# WireHub_2.net
KiCad netlist of a schematic drawn in EAGLE
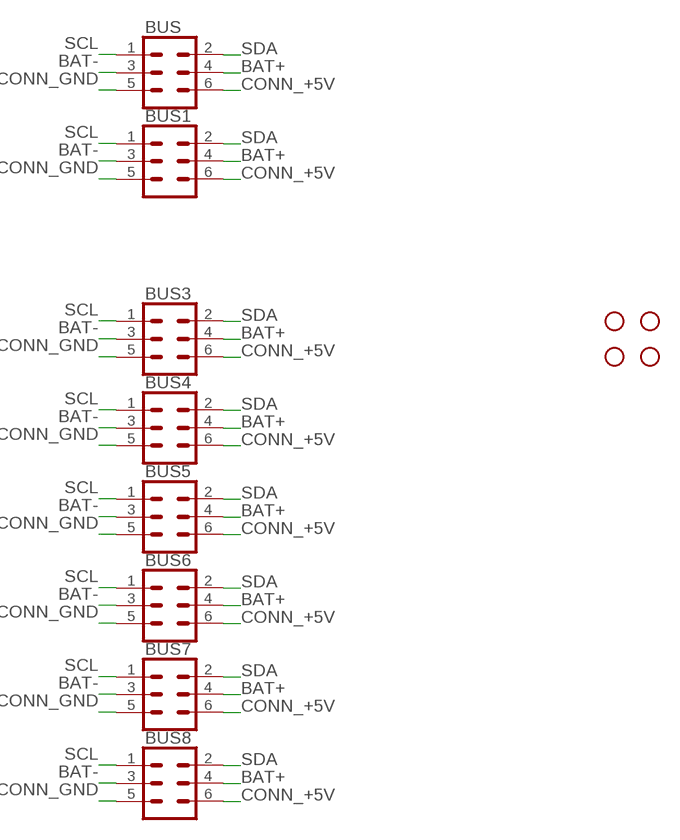
[diagram p0: schematic, sheet 1]

(export (version "E")
  (design (tool "Eeschema 10.0.6"))
  (components
    (comp (ref "BUS")
      (value "CONN_03X2SHROUD")
      (footprint "eagle-import:2X3-SHROUDED")
      (libsource (lib "eagle-import") (part "CONN_03X2SHROUD"))
    )
    (comp (ref "BUS1")
      (value "CONN_03X2SHROUD")
      (footprint "eagle-import:2X3-SHROUDED")
      (libsource (lib "eagle-import") (part "CONN_03X2SHROUD"))
    )
    (comp (ref "BUS3")
      (value "CONN_03X2SHROUD")
      (footprint "eagle-import:2X3-SHROUDED")
      (libsource (lib "eagle-import") (part "CONN_03X2SHROUD"))
    )
    (comp (ref "BUS4")
      (value "CONN_03X2SHROUD")
      (footprint "eagle-import:2X3-SHROUDED")
      (libsource (lib "eagle-import") (part "CONN_03X2SHROUD"))
    )
    (comp (ref "BUS5")
      (value "CONN_03X2SHROUD")
      (footprint "eagle-import:2X3-SHROUDED")
      (libsource (lib "eagle-import") (part "CONN_03X2SHROUD"))
    )
    (comp (ref "BUS6")
      (value "CONN_03X2SHROUD")
      (footprint "eagle-import:2X3-SHROUDED")
      (libsource (lib "eagle-import") (part "CONN_03X2SHROUD"))
    )
    (comp (ref "BUS7")
      (value "CONN_03X2SHROUD")
      (footprint "eagle-import:2X3-SHROUDED")
      (libsource (lib "eagle-import") (part "CONN_03X2SHROUD"))
    )
    (comp (ref "BUS8")
      (value "CONN_03X2SHROUD")
      (footprint "eagle-import:2X3-SHROUDED")
      (libsource (lib "eagle-import") (part "CONN_03X2SHROUD"))
    )
    (comp (ref "H1")
      (value "STAND-OFF")
      (footprint "eagle-import:STAND-OFF")
      (libsource (lib "eagle-import") (part "STAND-OFF"))
    )
    (comp (ref "H2")
      (value "STAND-OFF")
      (footprint "eagle-import:STAND-OFF")
      (libsource (lib "eagle-import") (part "STAND-OFF"))
    )
    (comp (ref "H3")
      (value "STAND-OFF")
      (footprint "eagle-import:STAND-OFF")
      (libsource (lib "eagle-import") (part "STAND-OFF"))
    )
    (comp (ref "H4")
      (value "STAND-OFF")
      (footprint "eagle-import:STAND-OFF")
      (libsource (lib "eagle-import") (part "STAND-OFF"))
    )
  )
  (nets
    (net (code "1") (name "/BAT+") (class "Default")
      (node (ref "BUS") (pin "4") (pinfunction "4_4") (pintype "bidirectional"))
      (node (ref "BUS1") (pin "4") (pinfunction "4_4") (pintype "bidirectional"))
      (node (ref "BUS3") (pin "4") (pinfunction "4_4") (pintype "bidirectional"))
      (node (ref "BUS4") (pin "4") (pinfunction "4_4") (pintype "bidirectional"))
      (node (ref "BUS5") (pin "4") (pinfunction "4_4") (pintype "bidirectional"))
      (node (ref "BUS6") (pin "4") (pinfunction "4_4") (pintype "bidirectional"))
      (node (ref "BUS7") (pin "4") (pinfunction "4_4") (pintype "bidirectional"))
      (node (ref "BUS8") (pin "4") (pinfunction "4_4") (pintype "bidirectional"))
    )
    (net (code "2") (name "/BAT-") (class "Default")
      (node (ref "BUS") (pin "3") (pinfunction "3_3") (pintype "bidirectional"))
      (node (ref "BUS1") (pin "3") (pinfunction "3_3") (pintype "bidirectional"))
      (node (ref "BUS3") (pin "3") (pinfunction "3_3") (pintype "bidirectional"))
      (node (ref "BUS4") (pin "3") (pinfunction "3_3") (pintype "bidirectional"))
      (node (ref "BUS5") (pin "3") (pinfunction "3_3") (pintype "bidirectional"))
      (node (ref "BUS6") (pin "3") (pinfunction "3_3") (pintype "bidirectional"))
      (node (ref "BUS7") (pin "3") (pinfunction "3_3") (pintype "bidirectional"))
      (node (ref "BUS8") (pin "3") (pinfunction "3_3") (pintype "bidirectional"))
    )
    (net (code "3") (name "/CONN_+5V") (class "Default")
      (node (ref "BUS") (pin "6") (pinfunction "6_6") (pintype "bidirectional"))
      (node (ref "BUS1") (pin "6") (pinfunction "6_6") (pintype "bidirectional"))
      (node (ref "BUS3") (pin "6") (pinfunction "6_6") (pintype "bidirectional"))
      (node (ref "BUS4") (pin "6") (pinfunction "6_6") (pintype "bidirectional"))
      (node (ref "BUS5") (pin "6") (pinfunction "6_6") (pintype "bidirectional"))
      (node (ref "BUS6") (pin "6") (pinfunction "6_6") (pintype "bidirectional"))
      (node (ref "BUS7") (pin "6") (pinfunction "6_6") (pintype "bidirectional"))
      (node (ref "BUS8") (pin "6") (pinfunction "6_6") (pintype "bidirectional"))
    )
    (net (code "4") (name "/CONN_GND") (class "Default")
      (node (ref "BUS") (pin "5") (pinfunction "5_5") (pintype "bidirectional"))
      (node (ref "BUS1") (pin "5") (pinfunction "5_5") (pintype "bidirectional"))
      (node (ref "BUS3") (pin "5") (pinfunction "5_5") (pintype "bidirectional"))
      (node (ref "BUS4") (pin "5") (pinfunction "5_5") (pintype "bidirectional"))
      (node (ref "BUS5") (pin "5") (pinfunction "5_5") (pintype "bidirectional"))
      (node (ref "BUS6") (pin "5") (pinfunction "5_5") (pintype "bidirectional"))
      (node (ref "BUS7") (pin "5") (pinfunction "5_5") (pintype "bidirectional"))
      (node (ref "BUS8") (pin "5") (pinfunction "5_5") (pintype "bidirectional"))
    )
    (net (code "5") (name "/SCL") (class "Default")
      (node (ref "BUS") (pin "1") (pinfunction "1_1") (pintype "bidirectional"))
      (node (ref "BUS1") (pin "1") (pinfunction "1_1") (pintype "bidirectional"))
      (node (ref "BUS3") (pin "1") (pinfunction "1_1") (pintype "bidirectional"))
      (node (ref "BUS4") (pin "1") (pinfunction "1_1") (pintype "bidirectional"))
      (node (ref "BUS5") (pin "1") (pinfunction "1_1") (pintype "bidirectional"))
      (node (ref "BUS6") (pin "1") (pinfunction "1_1") (pintype "bidirectional"))
      (node (ref "BUS7") (pin "1") (pinfunction "1_1") (pintype "bidirectional"))
      (node (ref "BUS8") (pin "1") (pinfunction "1_1") (pintype "bidirectional"))
    )
    (net (code "6") (name "/SDA") (class "Default")
      (node (ref "BUS") (pin "2") (pinfunction "2_2") (pintype "bidirectional"))
      (node (ref "BUS1") (pin "2") (pinfunction "2_2") (pintype "bidirectional"))
      (node (ref "BUS3") (pin "2") (pinfunction "2_2") (pintype "bidirectional"))
      (node (ref "BUS4") (pin "2") (pinfunction "2_2") (pintype "bidirectional"))
      (node (ref "BUS5") (pin "2") (pinfunction "2_2") (pintype "bidirectional"))
      (node (ref "BUS6") (pin "2") (pinfunction "2_2") (pintype "bidirectional"))
      (node (ref "BUS7") (pin "2") (pinfunction "2_2") (pintype "bidirectional"))
      (node (ref "BUS8") (pin "2") (pinfunction "2_2") (pintype "bidirectional"))
    )
  )
)
